# Tree_Batt.net
KiCad netlist of a schematic drawn in EAGLE
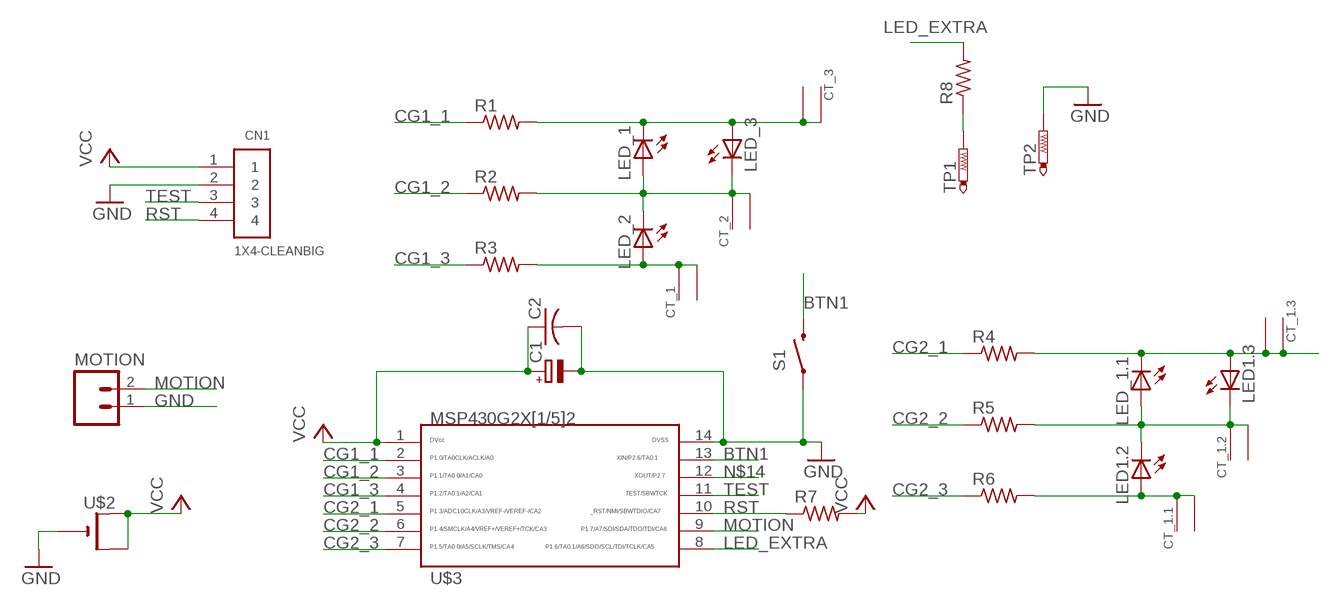
[diagram p0: schematic, sheet 1]

(export (version "E")
  (design (tool "Eeschema 10.0.6"))
  (components
    (comp (ref "C1")
      (value "CPOL-EUE2,5-6E")
      (footprint "eagle-import:E2,5-6E")
      (libsource (lib "eagle-import") (part "CPOL-EUE2,5-6E"))
    )
    (comp (ref "C2")
      (value "C-US025-024X044")
      (footprint "eagle-import:C025-024X044")
      (libsource (lib "eagle-import") (part "C-US025-024X044"))
    )
    (comp (ref "CN1")
      (value "1X4-CLEANBIG")
      (footprint "eagle-import:1X04-CLEANBIG")
      (libsource (lib "eagle-import") (part "1X4-CLEANBIG"))
    )
    (comp (ref "CT_1")
      (value "SMD_PAD")
      (footprint "eagle-import:5X5TREEPAD")
      (libsource (lib "eagle-import") (part "SMD_PAD"))
    )
    (comp (ref "CT_1.1")
      (value "SMD_PAD")
      (footprint "eagle-import:5X5TREEPAD")
      (libsource (lib "eagle-import") (part "SMD_PAD"))
    )
    (comp (ref "CT_1.2")
      (value "SMD_PAD")
      (footprint "eagle-import:5X5TREEPAD")
      (libsource (lib "eagle-import") (part "SMD_PAD"))
    )
    (comp (ref "CT_1.3")
      (value "SMD_PAD")
      (footprint "eagle-import:5X5TREEPAD")
      (libsource (lib "eagle-import") (part "SMD_PAD"))
    )
    (comp (ref "CT_2")
      (value "SMD_PAD")
      (footprint "eagle-import:5X5TREEPAD")
      (libsource (lib "eagle-import") (part "SMD_PAD"))
    )
    (comp (ref "CT_3")
      (value "SMD_PAD")
      (footprint "eagle-import:5X5TREEPAD")
      (libsource (lib "eagle-import") (part "SMD_PAD"))
    )
    (comp (ref "LED1.2")
      (value "LEDLED_CLEAN_EDGE")
      (footprint "eagle-import:1X02_NO_SILK")
      (libsource (lib "eagle-import") (part "LEDLED_CLEAN_EDGE"))
    )
    (comp (ref "LED1.3")
      (value "LEDLED_CLEAN_EDGE")
      (footprint "eagle-import:1X02_NO_SILK")
      (libsource (lib "eagle-import") (part "LEDLED_CLEAN_EDGE"))
    )
    (comp (ref "LED_1")
      (value "LEDLED_CLEAN_EDGE")
      (footprint "eagle-import:1X02_NO_SILK")
      (libsource (lib "eagle-import") (part "LEDLED_CLEAN_EDGE"))
    )
    (comp (ref "LED_1.1")
      (value "LEDLED_CLEAN_EDGE")
      (footprint "eagle-import:1X02_NO_SILK")
      (libsource (lib "eagle-import") (part "LEDLED_CLEAN_EDGE"))
    )
    (comp (ref "LED_2")
      (value "LEDLED_CLEAN_EDGE")
      (footprint "eagle-import:1X02_NO_SILK")
      (libsource (lib "eagle-import") (part "LEDLED_CLEAN_EDGE"))
    )
    (comp (ref "LED_3")
      (value "LEDLED_CLEAN_EDGE")
      (footprint "eagle-import:1X02_NO_SILK")
      (libsource (lib "eagle-import") (part "LEDLED_CLEAN_EDGE"))
    )
    (comp (ref "MOTION")
      (value "M021X02_NO_SILK")
      (footprint "eagle-import:1X02_NO_SILK")
      (libsource (lib "eagle-import") (part "M021X02_NO_SILK"))
    )
    (comp (ref "R1")
      (value "R-US_0204/7")
      (footprint "eagle-import:0204_7")
      (libsource (lib "eagle-import") (part "R-US_0204/7"))
    )
    (comp (ref "R2")
      (value "R-US_0204/7")
      (footprint "eagle-import:0204_7")
      (libsource (lib "eagle-import") (part "R-US_0204/7"))
    )
    (comp (ref "R3")
      (value "R-US_0204/7")
      (footprint "eagle-import:0204_7")
      (libsource (lib "eagle-import") (part "R-US_0204/7"))
    )
    (comp (ref "R4")
      (value "R-US_0204/7")
      (footprint "eagle-import:0204_7")
      (libsource (lib "eagle-import") (part "R-US_0204/7"))
    )
    (comp (ref "R5")
      (value "R-US_0204/7")
      (footprint "eagle-import:0204_7")
      (libsource (lib "eagle-import") (part "R-US_0204/7"))
    )
    (comp (ref "R6")
      (value "R-US_0204/7")
      (footprint "eagle-import:0204_7")
      (libsource (lib "eagle-import") (part "R-US_0204/7"))
    )
    (comp (ref "R7")
      (value "R-US_0204/7")
      (footprint "eagle-import:0204_7")
      (libsource (lib "eagle-import") (part "R-US_0204/7"))
    )
    (comp (ref "R8")
      (value "R-US_0204/7")
      (footprint "eagle-import:0204_7")
      (libsource (lib "eagle-import") (part "R-US_0204/7"))
    )
    (comp (ref "S1")
      (value "SWITCH-MOMENTARY-2-SMD-1101NE")
      (footprint "eagle-import:TACTILE-SWITCH-1101NE")
      (libsource (lib "eagle-import") (part "SWITCH-MOMENTARY-2-SMD-1101NE"))
    )
    (comp (ref "TP1")
      (value "PTR1PAD1-13")
      (footprint "eagle-import:P1-13")
      (libsource (lib "eagle-import") (part "PTR1PAD1-13"))
    )
    (comp (ref "TP2")
      (value "PTR1PAD1-13")
      (footprint "eagle-import:P1-13")
      (libsource (lib "eagle-import") (part "PTR1PAD1-13"))
    )
    (comp (ref "U$2")
      (value "CR2032SMT")
      (footprint "eagle-import:CR2032-SMD")
      (libsource (lib "eagle-import") (part "CR2032SMT"))
    )
    (comp (ref "U$3")
      (value "G2X[1/5]2---PW14")
      (footprint "eagle-import:PW14")
      (libsource (lib "eagle-import") (part "G2X[1/5]2---PW14"))
    )
  )
  (nets
    (net (code "1") (name "/BTN1") (class "Default")
      (node (ref "S1") (pin "P$2") (pinfunction "2_P$2") (pintype "passive"))
      (node (ref "U$3") (pin "13") (pinfunction "13_13") (pintype "bidirectional"))
    )
    (net (code "2") (name "/CG1_1") (class "Default")
      (node (ref "R1") (pin "1") (pinfunction "1_1") (pintype "passive"))
      (node (ref "U$3") (pin "2") (pinfunction "2_2") (pintype "bidirectional"))
    )
    (net (code "3") (name "/CG1_2") (class "Default")
      (node (ref "R2") (pin "1") (pinfunction "1_1") (pintype "passive"))
      (node (ref "U$3") (pin "3") (pinfunction "3_3") (pintype "bidirectional"))
    )
    (net (code "4") (name "/CG1_3") (class "Default")
      (node (ref "R3") (pin "1") (pinfunction "1_1") (pintype "passive"))
      (node (ref "U$3") (pin "4") (pinfunction "4_4") (pintype "bidirectional"))
    )
    (net (code "5") (name "/CG2_1") (class "Default")
      (node (ref "R4") (pin "1") (pinfunction "1_1") (pintype "passive"))
      (node (ref "U$3") (pin "5") (pinfunction "5_5") (pintype "bidirectional"))
    )
    (net (code "6") (name "/CG2_2") (class "Default")
      (node (ref "R5") (pin "1") (pinfunction "1_1") (pintype "passive"))
      (node (ref "U$3") (pin "6") (pinfunction "6_6") (pintype "bidirectional"))
    )
    (net (code "7") (name "/CG2_3") (class "Default")
      (node (ref "R6") (pin "1") (pinfunction "1_1") (pintype "passive"))
      (node (ref "U$3") (pin "7") (pinfunction "7_7") (pintype "bidirectional"))
    )
    (net (code "8") (name "/LED_EXTRA") (class "Default")
      (node (ref "R8") (pin "2") (pinfunction "2_2") (pintype "passive"))
      (node (ref "U$3") (pin "8") (pinfunction "8_8") (pintype "bidirectional"))
    )
    (net (code "9") (name "/MOTION") (class "Default")
      (node (ref "MOTION") (pin "2") (pinfunction "2_2") (pintype "passive"))
      (node (ref "U$3") (pin "9") (pinfunction "9_9") (pintype "bidirectional"))
    )
    (net (code "10") (name "/N$14") (class "Default")
      (node (ref "U$3") (pin "12") (pinfunction "12_12") (pintype "bidirectional"))
    )
    (net (code "11") (name "/RST") (class "Default")
      (node (ref "CN1") (pin "4") (pinfunction "4_4") (pintype "bidirectional"))
      (node (ref "R7") (pin "1") (pinfunction "1_1") (pintype "passive"))
      (node (ref "U$3") (pin "10") (pinfunction "10_10") (pintype "bidirectional"))
    )
    (net (code "12") (name "/TEST") (class "Default")
      (node (ref "CN1") (pin "3") (pinfunction "3_3") (pintype "bidirectional"))
      (node (ref "U$3") (pin "11") (pinfunction "11_11") (pintype "bidirectional"))
    )
    (net (code "13") (name "GND") (class "Default")
      (node (ref "C1") (pin "-") (pinfunction "-_-") (pintype "passive"))
      (node (ref "C2") (pin "2") (pinfunction "2_2") (pintype "passive"))
      (node (ref "CN1") (pin "2") (pinfunction "2_2") (pintype "bidirectional"))
      (node (ref "MOTION") (pin "1") (pinfunction "1_1") (pintype "passive"))
      (node (ref "S1") (pin "P$1") (pinfunction "1_P$1") (pintype "passive"))
      (node (ref "TP2") (pin "TP") (pinfunction "TP_TP") (pintype "input"))
      (node (ref "U$2") (pin "-") (pinfunction "-_-") (pintype "passive"))
      (node (ref "U$3") (pin "14") (pinfunction "14_14") (pintype "bidirectional"))
    )
    (net (code "14") (name "Net-(LED1.2-A)") (class "Default")
      (node (ref "CT_1.1") (pin "P$1") (pinfunction "P$1_P$1") (pintype "bidirectional"))
      (node (ref "CT_1.1") (pin "P$2") (pinfunction "P$2_P$2") (pintype "bidirectional"))
      (node (ref "LED1.2") (pin "1") (pinfunction "A_1") (pintype "passive"))
      (node (ref "R6") (pin "2") (pinfunction "2_2") (pintype "passive"))
    )
    (net (code "15") (name "Net-(LED1.2-C)") (class "Default")
      (node (ref "CT_1.2") (pin "P$1") (pinfunction "P$1_P$1") (pintype "bidirectional"))
      (node (ref "CT_1.2") (pin "P$2") (pinfunction "P$2_P$2") (pintype "bidirectional"))
      (node (ref "LED1.2") (pin "2") (pinfunction "C_2") (pintype "passive"))
      (node (ref "LED1.3") (pin "2") (pinfunction "C_2") (pintype "passive"))
      (node (ref "LED_1.1") (pin "1") (pinfunction "A_1") (pintype "passive"))
      (node (ref "R5") (pin "2") (pinfunction "2_2") (pintype "passive"))
    )
    (net (code "16") (name "Net-(LED1.3-A)") (class "Default")
      (node (ref "CT_1.3") (pin "P$1") (pinfunction "P$1_P$1") (pintype "bidirectional"))
      (node (ref "CT_1.3") (pin "P$2") (pinfunction "P$2_P$2") (pintype "bidirectional"))
      (node (ref "LED1.3") (pin "1") (pinfunction "A_1") (pintype "passive"))
      (node (ref "LED_1.1") (pin "2") (pinfunction "C_2") (pintype "passive"))
      (node (ref "R4") (pin "2") (pinfunction "2_2") (pintype "passive"))
    )
    (net (code "17") (name "Net-(LED_1-A)") (class "Default")
      (node (ref "CT_2") (pin "P$1") (pinfunction "P$1_P$1") (pintype "bidirectional"))
      (node (ref "CT_2") (pin "P$2") (pinfunction "P$2_P$2") (pintype "bidirectional"))
      (node (ref "LED_1") (pin "1") (pinfunction "A_1") (pintype "passive"))
      (node (ref "LED_2") (pin "2") (pinfunction "C_2") (pintype "passive"))
      (node (ref "LED_3") (pin "2") (pinfunction "C_2") (pintype "passive"))
      (node (ref "R2") (pin "2") (pinfunction "2_2") (pintype "passive"))
    )
    (net (code "18") (name "Net-(LED_1-C)") (class "Default")
      (node (ref "CT_3") (pin "P$1") (pinfunction "P$1_P$1") (pintype "bidirectional"))
      (node (ref "CT_3") (pin "P$2") (pinfunction "P$2_P$2") (pintype "bidirectional"))
      (node (ref "LED_1") (pin "2") (pinfunction "C_2") (pintype "passive"))
      (node (ref "LED_3") (pin "1") (pinfunction "A_1") (pintype "passive"))
      (node (ref "R1") (pin "2") (pinfunction "2_2") (pintype "passive"))
    )
    (net (code "19") (name "Net-(LED_2-A)") (class "Default")
      (node (ref "CT_1") (pin "P$1") (pinfunction "P$1_P$1") (pintype "bidirectional"))
      (node (ref "CT_1") (pin "P$2") (pinfunction "P$2_P$2") (pintype "bidirectional"))
      (node (ref "LED_2") (pin "1") (pinfunction "A_1") (pintype "passive"))
      (node (ref "R3") (pin "2") (pinfunction "2_2") (pintype "passive"))
    )
    (net (code "20") (name "Net-(R8-Pad1)") (class "Default")
      (node (ref "R8") (pin "1") (pinfunction "1_1") (pintype "passive"))
      (node (ref "TP1") (pin "TP") (pinfunction "TP_TP") (pintype "input"))
    )
    (net (code "21") (name "VCC") (class "Default")
      (node (ref "C1") (pin "+") (pinfunction "+_+") (pintype "passive"))
      (node (ref "C2") (pin "1") (pinfunction "1_1") (pintype "passive"))
      (node (ref "CN1") (pin "1") (pinfunction "1_1") (pintype "bidirectional"))
      (node (ref "R7") (pin "2") (pinfunction "2_2") (pintype "passive"))
      (node (ref "U$2") (pin "+$1") (pinfunction "+_+$1") (pintype "passive"))
      (node (ref "U$2") (pin "+$2") (pinfunction "+1_+$2") (pintype "passive"))
      (node (ref "U$3") (pin "1") (pinfunction "1_1") (pintype "bidirectional"))
    )
  )
)
